# Psion_Keyboard.net
KiCad netlist of a schematic drawn in EAGLE
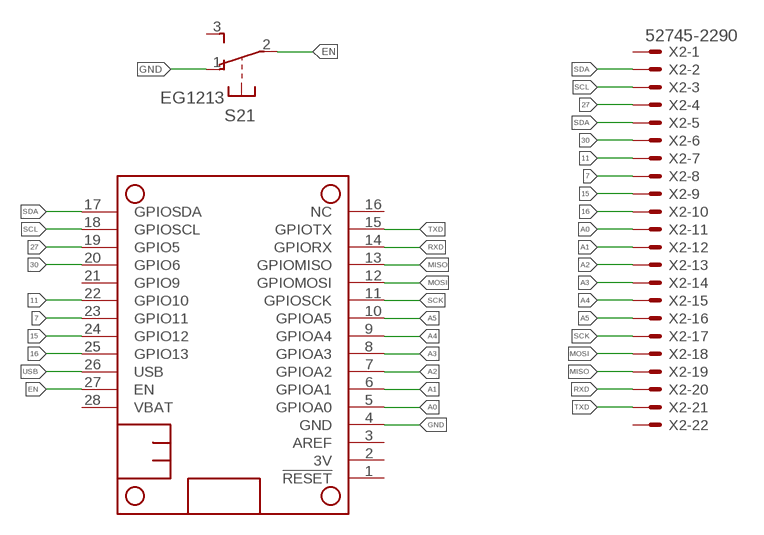
[diagram p0: schematic, sheet 1]

(export (version "E")
  (design (tool "Eeschema 10.0.6"))
  (components
    (comp (ref "MS1")
      (value "FEATHERWING_NODIM")
      (footprint "eagle-import:FEATHERWING_DIM")
      (libsource (lib "eagle-import") (part "FEATHERWING_NODIM"))
    )
    (comp (ref "S2")
      (value "EG1213")
      (footprint "eagle-import:EG1213")
      (libsource (lib "eagle-import") (part "EG1213"))
    )
    (comp (ref "X2")
      (value "52745-2290")
      (footprint "eagle-import:52745-2290")
      (fields (field (name "MF") "MOLEX"))
      (libsource (lib "eagle-import") (part "52745-2290"))
    )
  )
  (nets
    (net (code "1") (name "/3V") (class "Default")
      (node (ref "MS1") (pin "2") (pinfunction "3V_2") (pintype "power_in"))
    )
    (net (code "2") (name "/VBAT") (class "Default")
      (node (ref "MS1") (pin "28") (pinfunction "VBAT_28") (pintype "power_in"))
    )
    (net (code "3") (name "7") (class "Default")
      (node (ref "MS1") (pin "23") (pinfunction "GPIO11_23") (pintype "bidirectional"))
      (node (ref "X2") (pin "8") (pinfunction "S_8") (pintype "passive"))
    )
    (net (code "4") (name "11") (class "Default")
      (node (ref "MS1") (pin "22") (pinfunction "GPIO10_22") (pintype "bidirectional"))
      (node (ref "X2") (pin "7") (pinfunction "S_7") (pintype "passive"))
    )
    (net (code "5") (name "15") (class "Default")
      (node (ref "MS1") (pin "24") (pinfunction "GPIO12_24") (pintype "bidirectional"))
      (node (ref "X2") (pin "9") (pinfunction "S_9") (pintype "passive"))
    )
    (net (code "6") (name "16") (class "Default")
      (node (ref "MS1") (pin "25") (pinfunction "GPIO13_25") (pintype "bidirectional"))
      (node (ref "X2") (pin "10") (pinfunction "S_10") (pintype "passive"))
    )
    (net (code "7") (name "27") (class "Default")
      (node (ref "MS1") (pin "19") (pinfunction "GPIO5_19") (pintype "bidirectional"))
      (node (ref "X2") (pin "4") (pinfunction "S_4") (pintype "passive"))
    )
    (net (code "8") (name "30") (class "Default")
      (node (ref "MS1") (pin "20") (pinfunction "GPIO6_20") (pintype "bidirectional"))
      (node (ref "X2") (pin "6") (pinfunction "S_6") (pintype "passive"))
    )
    (net (code "9") (name "A0") (class "Default")
      (node (ref "MS1") (pin "5") (pinfunction "GPIOA0_5") (pintype "bidirectional"))
      (node (ref "X2") (pin "11") (pinfunction "S_11") (pintype "passive"))
    )
    (net (code "10") (name "A1") (class "Default")
      (node (ref "MS1") (pin "6") (pinfunction "GPIOA1_6") (pintype "bidirectional"))
      (node (ref "X2") (pin "12") (pinfunction "S_12") (pintype "passive"))
    )
    (net (code "11") (name "A2") (class "Default")
      (node (ref "MS1") (pin "7") (pinfunction "GPIOA2_7") (pintype "bidirectional"))
      (node (ref "X2") (pin "13") (pinfunction "S_13") (pintype "passive"))
    )
    (net (code "12") (name "A3") (class "Default")
      (node (ref "MS1") (pin "8") (pinfunction "GPIOA3_8") (pintype "bidirectional"))
      (node (ref "X2") (pin "14") (pinfunction "S_14") (pintype "passive"))
    )
    (net (code "13") (name "A4") (class "Default")
      (node (ref "MS1") (pin "9") (pinfunction "GPIOA4_9") (pintype "bidirectional"))
      (node (ref "X2") (pin "15") (pinfunction "S_15") (pintype "passive"))
    )
    (net (code "14") (name "A5") (class "Default")
      (node (ref "MS1") (pin "10") (pinfunction "GPIOA5_10") (pintype "bidirectional"))
      (node (ref "X2") (pin "16") (pinfunction "S_16") (pintype "passive"))
    )
    (net (code "15") (name "EN") (class "Default")
      (node (ref "MS1") (pin "27") (pinfunction "EN_27") (pintype "passive"))
      (node (ref "S2") (pin "2") (pinfunction "P_2") (pintype "passive"))
    )
    (net (code "16") (name "GND") (class "Default")
      (node (ref "MS1") (pin "4") (pinfunction "GND_4") (pintype "power_in"))
      (node (ref "S2") (pin "1") (pinfunction "O_1") (pintype "passive"))
    )
    (net (code "17") (name "MISO") (class "Default")
      (node (ref "MS1") (pin "13") (pinfunction "GPIOMISO_13") (pintype "bidirectional"))
      (node (ref "X2") (pin "19") (pinfunction "S_19") (pintype "passive"))
    )
    (net (code "18") (name "MOSI") (class "Default")
      (node (ref "MS1") (pin "12") (pinfunction "GPIOMOSI_12") (pintype "bidirectional"))
      (node (ref "X2") (pin "18") (pinfunction "S_18") (pintype "passive"))
    )
    (net (code "19") (name "RXD") (class "Default")
      (node (ref "MS1") (pin "14") (pinfunction "GPIORX_14") (pintype "bidirectional"))
      (node (ref "X2") (pin "20") (pinfunction "S_20") (pintype "passive"))
    )
    (net (code "20") (name "SCK") (class "Default")
      (node (ref "MS1") (pin "11") (pinfunction "GPIOSCK_11") (pintype "bidirectional"))
      (node (ref "X2") (pin "17") (pinfunction "S_17") (pintype "passive"))
    )
    (net (code "21") (name "SCL") (class "Default")
      (node (ref "MS1") (pin "18") (pinfunction "GPIOSCL_18") (pintype "bidirectional"))
      (node (ref "X2") (pin "3") (pinfunction "S_3") (pintype "passive"))
    )
    (net (code "22") (name "SDA") (class "Default")
      (node (ref "MS1") (pin "17") (pinfunction "GPIOSDA_17") (pintype "bidirectional"))
      (node (ref "X2") (pin "2") (pinfunction "S_2") (pintype "passive"))
      (node (ref "X2") (pin "5") (pinfunction "S_5") (pintype "passive"))
    )
    (net (code "23") (name "TXD") (class "Default")
      (node (ref "MS1") (pin "15") (pinfunction "GPIOTX_15") (pintype "bidirectional"))
      (node (ref "X2") (pin "21") (pinfunction "S_21") (pintype "passive"))
    )
    (net (code "24") (name "USB") (class "Default")
      (node (ref "MS1") (pin "26") (pinfunction "USB_26") (pintype "power_in"))
    )
    (net (code "25") (name "unconnected-(MS1-AREF-Pad3)") (class "Default")
      (node (ref "MS1") (pin "3") (pinfunction "AREF_3") (pintype "passive"))
    )
    (net (code "26") (name "unconnected-(MS1-GPIO9-Pad21)") (class "Default")
      (node (ref "MS1") (pin "21") (pinfunction "GPIO9_21") (pintype "bidirectional"))
    )
    (net (code "27") (name "unconnected-(MS1-NC-Pad16)") (class "Default")
      (node (ref "MS1") (pin "16") (pinfunction "NC_16") (pintype "passive"))
    )
    (net (code "28") (name "unconnected-(MS1-~{RESET}-Pad1)") (class "Default")
      (node (ref "MS1") (pin "1") (pinfunction "~{RESET}_1") (pintype "input"))
    )
    (net (code "29") (name "unconnected-(S2A-S-Pad3)") (class "Default")
      (node (ref "S2") (pin "3") (pinfunction "S_3") (pintype "passive"))
    )
    (net (code "30") (name "unconnected-(X2A-S-Pad1)") (class "Default")
      (node (ref "X2") (pin "1") (pinfunction "S_1") (pintype "passive"))
    )
    (net (code "31") (name "unconnected-(X2O-S-Pad22)") (class "Default")
      (node (ref "X2") (pin "22") (pinfunction "S_22") (pintype "passive"))
    )
  )
)
